# audio.net
KiCad netlist of a schematic drawn in Altium Designer
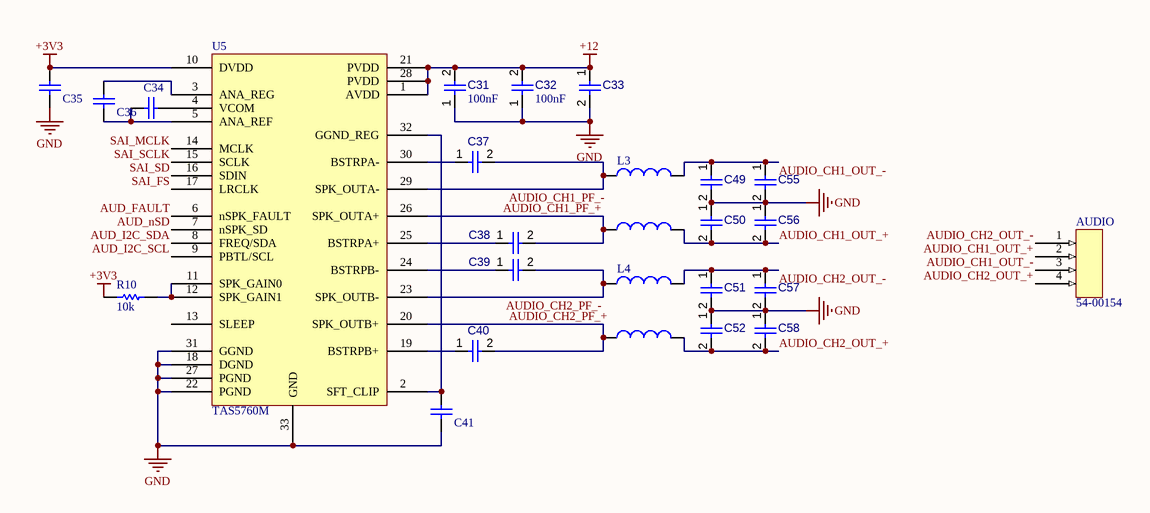
[diagram p0: audio.SchDoc]

(export (version "E")
  (design (tool "Eeschema 10.0.6"))
  (components
    (comp (ref "AUDIO")
      (value "54-00154")
      (footprint "54-00154-Footprint-1")
      (description "Conn Rcpt Fmale Pnl Mnt 4POS")
      (libsource (lib "Nicolespace") (part "54-00154"))
    )
    (comp (ref "C31")
      (value "100nF")
      (footprint "CAPC0402(1005)60_L")
      (description "Chip Capacitor, 100nF +/-20%, 25V, 0402, Thickness 0.6 mm")
      (fields (field (name "TOLERANCE") "10%") (field (name "Comment") "Capacitor 100nF +/-20% 25V 0402"))
      (libsource (lib "Nicolespace") (part "CAP-NP-2"))
    )
    (comp (ref "C32")
      (value "100nF")
      (footprint "CAPC0402(1005)60_L")
      (description "Chip Capacitor, 100nF +/-20%, 25V, 0402, Thickness 0.6 mm")
      (fields (field (name "TOLERANCE") "10%") (field (name "Comment") "Capacitor 100nF +/-20% 25V 0402"))
      (libsource (lib "Nicolespace") (part "CAP-NP-2"))
    )
    (comp (ref "C33")
      (value "T59EE477M016C0025")
      (footprint "CAPC7343X43N")
      (libsource (lib "Nicolespace") (part "CAP-NP-2"))
    )
    (comp (ref "C34")
      (value "TACL105M016XTA")
      (footprint "CAPC1609X100X15NL20")
      (fields (field (name "MANUFACTURER") "AVX Interconnect / Elco"))
      (libsource (lib "Altium Content Vault") (part "CAP"))
    )
    (comp (ref "C35")
      (value "TACL105M016XTA")
      (footprint "CAPC1609X100X15NL20")
      (fields (field (name "MANUFACTURER") "AVX Interconnect / Elco"))
      (libsource (lib "Altium Content Vault") (part "CAP"))
    )
    (comp (ref "C36")
      (value "TACL105M016XTA")
      (footprint "CAPC1609X100X15NL20")
      (fields (field (name "MANUFACTURER") "AVX Interconnect / Elco"))
      (libsource (lib "Altium Content Vault") (part "CAP"))
    )
    (comp (ref "C37")
      (value "16MU224MZ22012")
      (footprint "CAPC2014X10N")
      (description "Film Capacitor, 16V, 20% +Tol, 20% -Tol, 0.22uF, Surface Mount, 0805")
      (libsource (lib "Nicolespace") (part "CAP-NP-2"))
    )
    (comp (ref "C38")
      (value "16MU224MZ22012")
      (footprint "CAPC2014X10N")
      (description "Film Capacitor, 16V, 20% +Tol, 20% -Tol, 0.22uF, Surface Mount, 0805")
      (libsource (lib "Nicolespace") (part "CAP-NP-2"))
    )
    (comp (ref "C39")
      (value "16MU224MZ22012")
      (footprint "CAPC2014X10N")
      (description "Film Capacitor, 16V, 20% +Tol, 20% -Tol, 0.22uF, Surface Mount, 0805")
      (libsource (lib "Nicolespace") (part "CAP-NP-2"))
    )
    (comp (ref "C40")
      (value "16MU224MZ22012")
      (footprint "CAPC2014X10N")
      (description "Film Capacitor, 16V, 20% +Tol, 20% -Tol, 0.22uF, Surface Mount, 0805")
      (libsource (lib "Nicolespace") (part "CAP-NP-2"))
    )
    (comp (ref "C41")
      (value "TACL105M016XTA")
      (footprint "CAPC1609X100X15NL20")
      (fields (field (name "MANUFACTURER") "AVX Interconnect / Elco"))
      (libsource (lib "Altium Content Vault") (part "CAP"))
    )
    (comp (ref "C49")
      (value "16MU224MZ22012")
      (footprint "CAPC2014X10N")
      (description "Film Capacitor, 16V, 20% +Tol, 20% -Tol, 0.22uF, Surface Mount, 0805")
      (libsource (lib "Nicolespace") (part "CAP-NP-2"))
    )
    (comp (ref "C50")
      (value "16MU224MZ22012")
      (footprint "CAPC2014X10N")
      (description "Film Capacitor, 16V, 20% +Tol, 20% -Tol, 0.22uF, Surface Mount, 0805")
      (libsource (lib "Nicolespace") (part "CAP-NP-2"))
    )
    (comp (ref "C51")
      (value "16MU224MZ22012")
      (footprint "CAPC2014X10N")
      (description "Film Capacitor, 16V, 20% +Tol, 20% -Tol, 0.22uF, Surface Mount, 0805")
      (libsource (lib "Nicolespace") (part "CAP-NP-2"))
    )
    (comp (ref "C52")
      (value "16MU224MZ22012")
      (footprint "CAPC2014X10N")
      (description "Film Capacitor, 16V, 20% +Tol, 20% -Tol, 0.22uF, Surface Mount, 0805")
      (libsource (lib "Nicolespace") (part "CAP-NP-2"))
    )
    (comp (ref "C55")
      (value "16MU224MZ22012")
      (footprint "CAPC2014X10N")
      (description "Film Capacitor, 16V, 20% +Tol, 20% -Tol, 0.22uF, Surface Mount, 0805")
      (libsource (lib "Nicolespace") (part "CAP-NP-2"))
    )
    (comp (ref "C56")
      (value "16MU224MZ22012")
      (footprint "CAPC2014X10N")
      (description "Film Capacitor, 16V, 20% +Tol, 20% -Tol, 0.22uF, Surface Mount, 0805")
      (libsource (lib "Nicolespace") (part "CAP-NP-2"))
    )
    (comp (ref "C57")
      (value "16MU224MZ22012")
      (footprint "CAPC2014X10N")
      (description "Film Capacitor, 16V, 20% +Tol, 20% -Tol, 0.22uF, Surface Mount, 0805")
      (libsource (lib "Nicolespace") (part "CAP-NP-2"))
    )
    (comp (ref "C58")
      (value "16MU224MZ22012")
      (footprint "CAPC2014X10N")
      (description "Film Capacitor, 16V, 20% +Tol, 20% -Tol, 0.22uF, Surface Mount, 0805")
      (libsource (lib "Nicolespace") (part "CAP-NP-2"))
    )
    (comp (ref "L3")
      (value "ACDL2V0910-100-R")
      (footprint "ACDL2V0910-100-R-Footprint-1")
      (description "2 ch inductor for audio")
      (libsource (lib "Nicolespace") (part "IND-2"))
    )
    (comp (ref "L4")
      (value "ACDL2V0910-100-R")
      (footprint "ACDL2V0910-100-R-Footprint-1")
      (description "2 ch inductor for audio")
      (libsource (lib "Nicolespace") (part "IND-2"))
    )
    (comp (ref "R10")
      (value "10k")
      (footprint "RESC1609X50X30NL8T20")
      (description "Chip Resistor, 10 KOhm, +/- 1%, 100 mW, -55 to 155 degC, 0603 (1608 Metric), RoHS, Tape and Reel")
      (fields (field (name "MANUFACTURER") "Vishay Semiconductor"))
      (libsource (lib "Altium Content Vault") (part "RES-2"))
    )
    (comp (ref "U5")
      (value "TAS5760M")
      (footprint "TSOP65P810X120_HS-33N")
      (libsource (lib "Nicolespace") (part "TAS5760M-Symbol-1"))
    )
  )
  (nets
    (net (code "1") (name "+3V3") (class "Default")
      (node (ref "C35") (pin "2") (pinfunction "2_2") (pintype "passive"))
      (node (ref "R10") (pin "2") (pinfunction "2_2") (pintype "passive"))
      (node (ref "U5") (pin "10") (pinfunction "DVDD_10") (pintype "passive"))
    )
    (net (code "2") (name "+12") (class "Default")
      (node (ref "C31") (pin "2") (pinfunction "2_2") (pintype "passive"))
      (node (ref "C32") (pin "2") (pinfunction "2_2") (pintype "passive"))
      (node (ref "C33") (pin "1") (pinfunction "1_1") (pintype "passive"))
      (node (ref "U5") (pin "1") (pinfunction "AVDD_1") (pintype "passive"))
      (node (ref "U5") (pin "21") (pinfunction "PVDD_21") (pintype "passive"))
      (node (ref "U5") (pin "28") (pinfunction "PVDD_28") (pintype "passive"))
    )
    (net (code "3") (name "/AUDIO_CH1_OUT_+") (class "Default")
      (node (ref "AUDIO") (pin "2") (pintype "input"))
      (node (ref "C50") (pin "2") (pinfunction "2_2") (pintype "passive"))
      (node (ref "C56") (pin "2") (pinfunction "2_2") (pintype "passive"))
      (node (ref "L3") (pin "4") (pinfunction "2_4") (pintype "passive"))
    )
    (net (code "4") (name "/AUDIO_CH1_OUT_-") (class "Default")
      (node (ref "AUDIO") (pin "3") (pintype "input"))
      (node (ref "C49") (pin "1") (pinfunction "1_1") (pintype "passive"))
      (node (ref "C55") (pin "1") (pinfunction "1_1") (pintype "passive"))
      (node (ref "L3") (pin "2") (pinfunction "2_2") (pintype "passive"))
    )
    (net (code "5") (name "/AUDIO_CH1_PF_+") (class "Default")
      (node (ref "C38") (pin "2") (pinfunction "2_2") (pintype "passive"))
      (node (ref "L3") (pin "3") (pinfunction "1_3") (pintype "passive"))
      (node (ref "U5") (pin "26") (pinfunction "SPK_OUTA+_26") (pintype "passive"))
    )
    (net (code "6") (name "/AUDIO_CH1_PF_-") (class "Default")
      (node (ref "C37") (pin "2") (pinfunction "2_2") (pintype "passive"))
      (node (ref "L3") (pin "1") (pinfunction "1_1") (pintype "passive"))
      (node (ref "U5") (pin "29") (pinfunction "SPK_OUTA-_29") (pintype "passive"))
    )
    (net (code "7") (name "/AUDIO_CH2_OUT_+") (class "Default")
      (node (ref "AUDIO") (pin "4") (pintype "input"))
      (node (ref "C52") (pin "2") (pinfunction "2_2") (pintype "passive"))
      (node (ref "C58") (pin "2") (pinfunction "2_2") (pintype "passive"))
      (node (ref "L4") (pin "4") (pinfunction "2_4") (pintype "passive"))
    )
    (net (code "8") (name "/AUDIO_CH2_OUT_-") (class "Default")
      (node (ref "AUDIO") (pin "1") (pintype "input"))
      (node (ref "C51") (pin "1") (pinfunction "1_1") (pintype "passive"))
      (node (ref "C57") (pin "1") (pinfunction "1_1") (pintype "passive"))
      (node (ref "L4") (pin "2") (pinfunction "2_2") (pintype "passive"))
    )
    (net (code "9") (name "/AUDIO_CH2_PF_+") (class "Default")
      (node (ref "C40") (pin "2") (pinfunction "2_2") (pintype "passive"))
      (node (ref "L4") (pin "3") (pinfunction "1_3") (pintype "passive"))
      (node (ref "U5") (pin "20") (pinfunction "SPK_OUTB+_20") (pintype "passive"))
    )
    (net (code "10") (name "/AUDIO_CH2_PF_-") (class "Default")
      (node (ref "C39") (pin "2") (pinfunction "2_2") (pintype "passive"))
      (node (ref "L4") (pin "1") (pinfunction "1_1") (pintype "passive"))
      (node (ref "U5") (pin "23") (pinfunction "SPK_OUTB-_23") (pintype "passive"))
    )
    (net (code "11") (name "/AUD_FAULT") (class "Default")
      (node (ref "U5") (pin "6") (pinfunction "nSPK_FAULT_6") (pintype "passive"))
    )
    (net (code "12") (name "/AUD_I2C_SCL") (class "Default")
      (node (ref "U5") (pin "9") (pinfunction "PBTL/SCL_9") (pintype "passive"))
    )
    (net (code "13") (name "/AUD_I2C_SDA") (class "Default")
      (node (ref "U5") (pin "8") (pinfunction "FREQ/SDA_8") (pintype "passive"))
    )
    (net (code "14") (name "/AUD_nSD") (class "Default")
      (node (ref "U5") (pin "7") (pinfunction "nSPK_SD_7") (pintype "passive"))
    )
    (net (code "15") (name "/SAI_FS") (class "Default")
      (node (ref "U5") (pin "17") (pinfunction "LRCLK_17") (pintype "passive"))
    )
    (net (code "16") (name "/SAI_MCLK") (class "Default")
      (node (ref "U5") (pin "14") (pinfunction "MCLK_14") (pintype "passive"))
    )
    (net (code "17") (name "/SAI_SCLK") (class "Default")
      (node (ref "U5") (pin "15") (pinfunction "SCLK_15") (pintype "passive"))
    )
    (net (code "18") (name "/SAI_SD") (class "Default")
      (node (ref "U5") (pin "16") (pinfunction "SDIN_16") (pintype "passive"))
    )
    (net (code "19") (name "GND") (class "Default")
      (node (ref "C31") (pin "1") (pinfunction "1_1") (pintype "passive"))
      (node (ref "C32") (pin "1") (pinfunction "1_1") (pintype "passive"))
      (node (ref "C33") (pin "2") (pinfunction "2_2") (pintype "passive"))
      (node (ref "C35") (pin "1") (pinfunction "1_1") (pintype "passive"))
      (node (ref "C41") (pin "2") (pinfunction "2_2") (pintype "passive"))
      (node (ref "C49") (pin "2") (pinfunction "2_2") (pintype "passive"))
      (node (ref "C50") (pin "1") (pinfunction "1_1") (pintype "passive"))
      (node (ref "C51") (pin "2") (pinfunction "2_2") (pintype "passive"))
      (node (ref "C52") (pin "1") (pinfunction "1_1") (pintype "passive"))
      (node (ref "C55") (pin "2") (pinfunction "2_2") (pintype "passive"))
      (node (ref "C56") (pin "1") (pinfunction "1_1") (pintype "passive"))
      (node (ref "C57") (pin "2") (pinfunction "2_2") (pintype "passive"))
      (node (ref "C58") (pin "1") (pinfunction "1_1") (pintype "passive"))
      (node (ref "U5") (pin "18") (pinfunction "DGND_18") (pintype "passive"))
      (node (ref "U5") (pin "22") (pinfunction "PGND_22") (pintype "passive"))
      (node (ref "U5") (pin "27") (pinfunction "PGND_27") (pintype "passive"))
      (node (ref "U5") (pin "31") (pinfunction "GGND_31") (pintype "passive"))
      (node (ref "U5") (pin "33") (pinfunction "GND_33") (pintype "passive"))
    )
    (net (code "20") (name "Net-(U5-ANA_REF)") (class "Default")
      (node (ref "C34") (pin "1") (pinfunction "1_1") (pintype "passive"))
      (node (ref "C36") (pin "1") (pinfunction "1_1") (pintype "passive"))
      (node (ref "U5") (pin "5") (pinfunction "ANA_REF_5") (pintype "passive"))
    )
    (net (code "21") (name "Net-(U5-ANA_REG)") (class "Default")
      (node (ref "C36") (pin "2") (pinfunction "2_2") (pintype "passive"))
      (node (ref "U5") (pin "3") (pinfunction "ANA_REG_3") (pintype "passive"))
    )
    (net (code "22") (name "Net-(U5-BSTRPA+)") (class "Default")
      (node (ref "C38") (pin "1") (pinfunction "1_1") (pintype "passive"))
      (node (ref "U5") (pin "25") (pinfunction "BSTRPA+_25") (pintype "passive"))
    )
    (net (code "23") (name "Net-(U5-BSTRPA-)") (class "Default")
      (node (ref "C37") (pin "1") (pinfunction "1_1") (pintype "passive"))
      (node (ref "U5") (pin "30") (pinfunction "BSTRPA-_30") (pintype "passive"))
    )
    (net (code "24") (name "Net-(U5-BSTRPB+)") (class "Default")
      (node (ref "C40") (pin "1") (pinfunction "1_1") (pintype "passive"))
      (node (ref "U5") (pin "19") (pinfunction "BSTRPB+_19") (pintype "passive"))
    )
    (net (code "25") (name "Net-(U5-BSTRPB-)") (class "Default")
      (node (ref "C39") (pin "1") (pinfunction "1_1") (pintype "passive"))
      (node (ref "U5") (pin "24") (pinfunction "BSTRPB-_24") (pintype "passive"))
    )
    (net (code "26") (name "Net-(U5-GGND_REG)") (class "Default")
      (node (ref "C41") (pin "1") (pinfunction "1_1") (pintype "passive"))
      (node (ref "U5") (pin "2") (pinfunction "SFT_CLIP_2") (pintype "passive"))
      (node (ref "U5") (pin "32") (pinfunction "GGND_REG_32") (pintype "passive"))
    )
    (net (code "27") (name "Net-(U5-SPK_GAIN0)") (class "Default")
      (node (ref "R10") (pin "1") (pinfunction "1_1") (pintype "passive"))
      (node (ref "U5") (pin "11") (pinfunction "SPK_GAIN0_11") (pintype "passive"))
      (node (ref "U5") (pin "12") (pinfunction "SPK_GAIN1_12") (pintype "passive"))
    )
    (net (code "28") (name "Net-(U5-VCOM)") (class "Default")
      (node (ref "C34") (pin "2") (pinfunction "2_2") (pintype "passive"))
      (node (ref "U5") (pin "4") (pinfunction "VCOM_4") (pintype "passive"))
    )
    (net (code "29") (name "unconnected-(U5-SLEEP-Pad13)") (class "Default")
      (node (ref "U5") (pin "13") (pinfunction "SLEEP_13") (pintype "passive"))
    )
  )
)
